# Motor_Buttons.net
KiCad netlist of a schematic drawn in Altium Designer
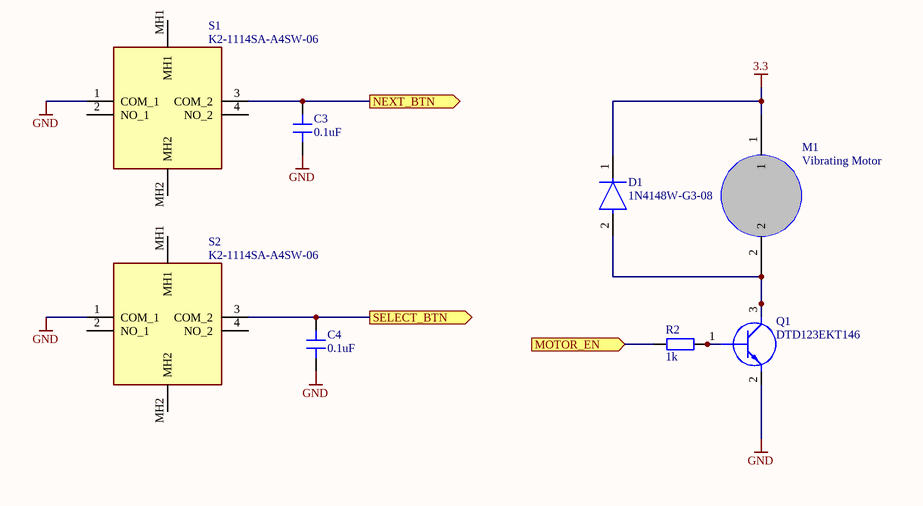
[diagram p0: Motor_Buttons.SchDoc]

(export (version "E")
  (design (tool "Eeschema 10.0.6"))
  (components
    (comp (ref "C3") (value "0.1uF") (footprint "0603_CAP") (libsource (lib "passive_components") (part "C")))
    (comp (ref "C4") (value "0.1uF") (footprint "0603_CAP") (libsource (lib "passive_components") (part "C")))
    (comp (ref "D1")
      (value "1N4148W-G3-08")
      (footprint "SOD3716X135N")
      (description "1N4148W-G3-08 Rectifier Diode, 1 Phase, 1 Element, 0.15A, 100V V(RRM), Silicon")
      (libsource (lib "Diode") (part "CMP-00030-46456310-1"))
    )
    (comp (ref "M1")
      (value "Vibrating Motor")
      (footprint "Motor")
      (libsource (lib "Motor") (part "Component_1"))
    )
    (comp (ref "Q1")
      (value "DTD123EKT146")
      (footprint "FP-SS8050-G-IPC_A")
      (description "Transistor BJT NPN")
      (fields (field (name "MOUSER PART NUMBER") "755-DTD123EKT146"))
      (libsource (lib "test") (part "DTD123EKT146"))
    )
    (comp (ref "R2") (value "1k") (footprint "0402_RES") (libsource (lib "passive_components") (part "R")))
    (comp (ref "S1")
      (value "K2-1114SA-A4SW-06")
      (footprint "K21114SAA4SW06")
      (description "Switch")
      (libsource (lib "PushButton_v01") (part "K2-1114SA-A4SW-06"))
    )
    (comp (ref "S2")
      (value "K2-1114SA-A4SW-06")
      (footprint "K21114SAA4SW06")
      (description "Switch")
      (libsource (lib "PushButton_v01") (part "K2-1114SA-A4SW-06"))
    )
  )
  (nets
    (net (code "1") (name "/MOTOR_EN") (class "Default")
      (node (ref "R2") (pin "1") (pinfunction "25_1") (pintype "passive"))
    )
    (net (code "2") (name "/NEXT_BTN") (class "Default")
      (node (ref "C3") (pin "1") (pinfunction "1_1") (pintype "passive"))
      (node (ref "S1") (pin "3") (pinfunction "COM_2_3") (pintype "passive"))
    )
    (net (code "3") (name "/SELECT_BTN") (class "Default")
      (node (ref "C4") (pin "1") (pinfunction "1_1") (pintype "passive"))
      (node (ref "S2") (pin "3") (pinfunction "COM_2_3") (pintype "passive"))
    )
    (net (code "4") (name "3.3") (class "Default")
      (node (ref "D1") (pin "1") (pinfunction "C_1") (pintype "passive"))
      (node (ref "M1") (pin "1") (pinfunction "1_1") (pintype "passive"))
    )
    (net (code "5") (name "GND") (class "Default")
      (node (ref "C3") (pin "2") (pinfunction "28_2") (pintype "passive"))
      (node (ref "C4") (pin "2") (pinfunction "28_2") (pintype "passive"))
      (node (ref "Q1") (pin "2") (pinfunction "E_2") (pintype "passive"))
      (node (ref "S1") (pin "1") (pinfunction "COM_1_1") (pintype "passive"))
      (node (ref "S2") (pin "1") (pinfunction "COM_1_1") (pintype "passive"))
    )
    (net (code "6") (name "Net-(D1-A)") (class "Default")
      (node (ref "D1") (pin "2") (pinfunction "A_2") (pintype "passive"))
      (node (ref "M1") (pin "2") (pinfunction "2_2") (pintype "passive"))
      (node (ref "Q1") (pin "3") (pinfunction "C_3") (pintype "passive"))
    )
    (net (code "7") (name "Net-(Q1-B)") (class "Default")
      (node (ref "Q1") (pin "1") (pinfunction "B_1") (pintype "passive"))
      (node (ref "R2") (pin "2") (pinfunction "26_2") (pintype "passive"))
    )
    (net (code "8") (name "unconnected-(S1-NO_1-Pad2)") (class "Default")
      (node (ref "S1") (pin "2") (pinfunction "NO_1_2") (pintype "passive"))
    )
    (net (code "9") (name "unconnected-(S1-NO_2-Pad4)") (class "Default")
      (node (ref "S1") (pin "4") (pinfunction "NO_2_4") (pintype "passive"))
    )
    (net (code "10") (name "unconnected-(S1-PadMH1)") (class "Default")
      (node (ref "S1") (pin "MH1") (pinfunction "MH1_MH1") (pintype "passive"))
    )
    (net (code "11") (name "unconnected-(S1-PadMH2)") (class "Default")
      (node (ref "S1") (pin "MH2") (pinfunction "MH2_MH2") (pintype "passive"))
    )
    (net (code "12") (name "unconnected-(S2-NO_1-Pad2)") (class "Default")
      (node (ref "S2") (pin "2") (pinfunction "NO_1_2") (pintype "passive"))
    )
    (net (code "13") (name "unconnected-(S2-NO_2-Pad4)") (class "Default")
      (node (ref "S2") (pin "4") (pinfunction "NO_2_4") (pintype "passive"))
    )
    (net (code "14") (name "unconnected-(S2-PadMH1)") (class "Default")
      (node (ref "S2") (pin "MH1") (pinfunction "MH1_MH1") (pintype "passive"))
    )
    (net (code "15") (name "unconnected-(S2-PadMH2)") (class "Default")
      (node (ref "S2") (pin "MH2") (pinfunction "MH2_MH2") (pintype "passive"))
    )
  )
)
